# SOC_1_0.net
KiCad netlist of a schematic drawn in EAGLE
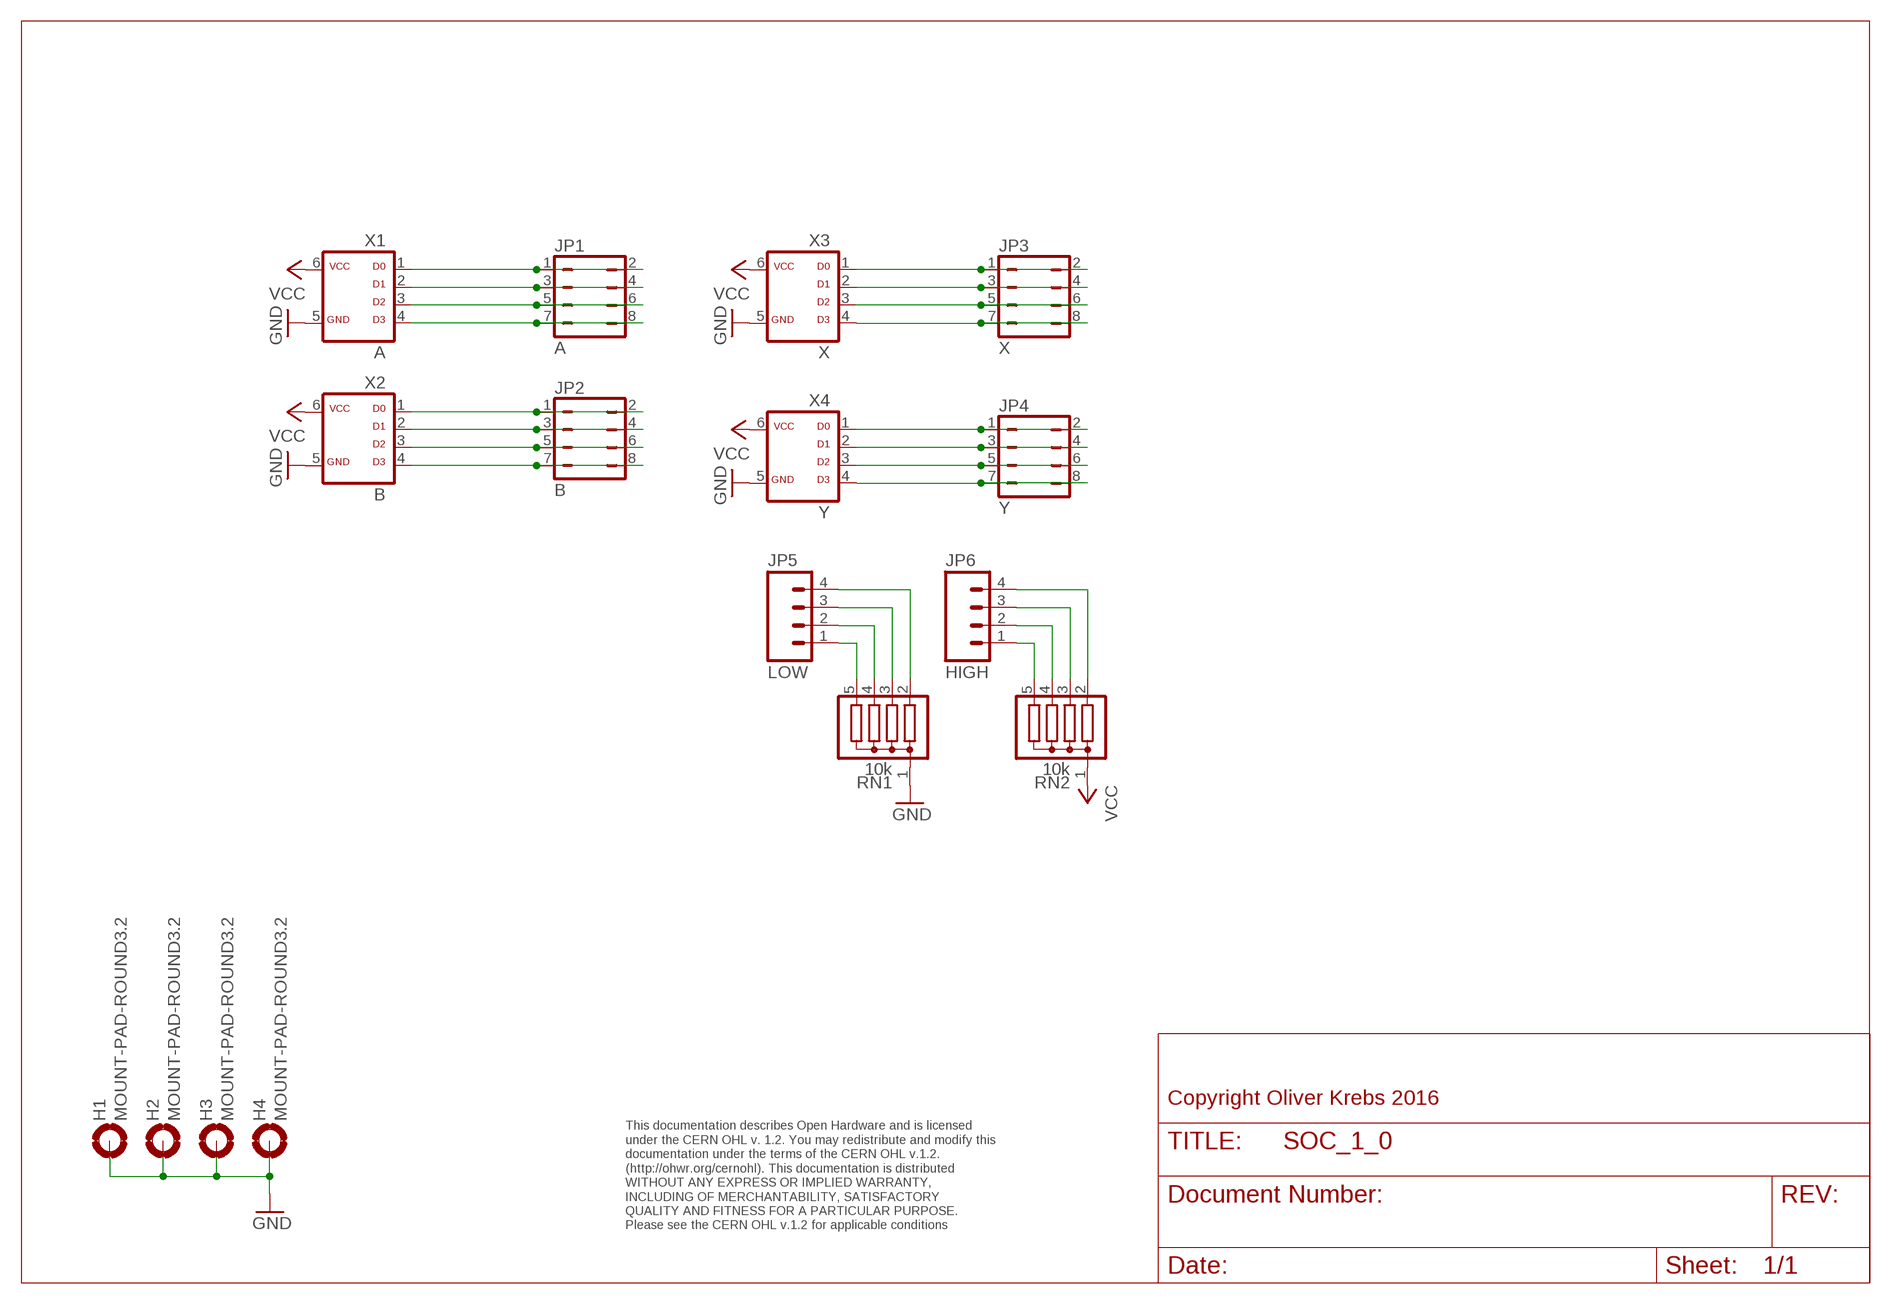
[diagram p0: schematic, sheet 1]

(export (version "E")
  (design (tool "Eeschema 10.0.6"))
  (components
    (comp (ref "H1")
      (value "MOUNT-PAD-ROUND3.2")
      (footprint "eagle-import:3,2-PAD")
      (libsource (lib "eagle-import") (part "MOUNT-PAD-ROUND3.2"))
    )
    (comp (ref "H2")
      (value "MOUNT-PAD-ROUND3.2")
      (footprint "eagle-import:3,2-PAD")
      (libsource (lib "eagle-import") (part "MOUNT-PAD-ROUND3.2"))
    )
    (comp (ref "H3")
      (value "MOUNT-PAD-ROUND3.2")
      (footprint "eagle-import:3,2-PAD")
      (libsource (lib "eagle-import") (part "MOUNT-PAD-ROUND3.2"))
    )
    (comp (ref "H4")
      (value "MOUNT-PAD-ROUND3.2")
      (footprint "eagle-import:3,2-PAD")
      (libsource (lib "eagle-import") (part "MOUNT-PAD-ROUND3.2"))
    )
    (comp (ref "JP1")
      (value "A")
      (footprint "eagle-import:JP4Q")
      (libsource (lib "eagle-import") (part "JP4Q"))
    )
    (comp (ref "JP2")
      (value "B")
      (footprint "eagle-import:JP4Q")
      (libsource (lib "eagle-import") (part "JP4Q"))
    )
    (comp (ref "JP3")
      (value "X")
      (footprint "eagle-import:JP4Q")
      (libsource (lib "eagle-import") (part "JP4Q"))
    )
    (comp (ref "JP4")
      (value "Y")
      (footprint "eagle-import:JP4Q")
      (libsource (lib "eagle-import") (part "JP4Q"))
    )
    (comp (ref "JP5")
      (value "LOW")
      (footprint "eagle-import:1X04")
      (libsource (lib "eagle-import") (part "M04PTH"))
    )
    (comp (ref "JP6")
      (value "HIGH")
      (footprint "eagle-import:1X04")
      (libsource (lib "eagle-import") (part "M04PTH"))
    )
    (comp (ref "RN1")
      (value "10k")
      (footprint "eagle-import:SIL5")
      (libsource (lib "eagle-import") (part "G04R"))
    )
    (comp (ref "RN2")
      (value "10k")
      (footprint "eagle-import:SIL5")
      (libsource (lib "eagle-import") (part "G04R"))
    )
    (comp (ref "X1")
      (value "A")
      (footprint "eagle-import:ML-6")
      (libsource (lib "eagle-import") (part "ML6D"))
    )
    (comp (ref "X2")
      (value "B")
      (footprint "eagle-import:ML-6")
      (libsource (lib "eagle-import") (part "ML6D"))
    )
    (comp (ref "X3")
      (value "X")
      (footprint "eagle-import:ML-6")
      (libsource (lib "eagle-import") (part "ML6D"))
    )
    (comp (ref "X4")
      (value "Y")
      (footprint "eagle-import:ML-6")
      (libsource (lib "eagle-import") (part "ML6D"))
    )
  )
  (nets
    (net (code "1") (name "GND") (class "Default")
      (node (ref "H1") (pin "B3,2") (pinfunction "MOUNT_B3,2") (pintype "passive"))
      (node (ref "H2") (pin "B3,2") (pinfunction "MOUNT_B3,2") (pintype "passive"))
      (node (ref "H3") (pin "B3,2") (pinfunction "MOUNT_B3,2") (pintype "passive"))
      (node (ref "H4") (pin "B3,2") (pinfunction "MOUNT_B3,2") (pintype "passive"))
      (node (ref "RN1") (pin "1") (pinfunction "1_1") (pintype "passive"))
      (node (ref "X1") (pin "5") (pinfunction "5_5") (pintype "passive"))
      (node (ref "X2") (pin "5") (pinfunction "5_5") (pintype "passive"))
      (node (ref "X3") (pin "5") (pinfunction "5_5") (pintype "passive"))
      (node (ref "X4") (pin "5") (pinfunction "5_5") (pintype "passive"))
    )
    (net (code "2") (name "Net-(JP1-Pad1)") (class "Default")
      (node (ref "JP1") (pin "1") (pinfunction "1_1") (pintype "passive"))
      (node (ref "JP1") (pin "2") (pinfunction "2_2") (pintype "passive"))
      (node (ref "X1") (pin "1") (pinfunction "1_1") (pintype "passive"))
    )
    (net (code "3") (name "Net-(JP1-Pad3)") (class "Default")
      (node (ref "JP1") (pin "3") (pinfunction "3_3") (pintype "passive"))
      (node (ref "JP1") (pin "4") (pinfunction "4_4") (pintype "passive"))
      (node (ref "X1") (pin "2") (pinfunction "2_2") (pintype "passive"))
    )
    (net (code "4") (name "Net-(JP1-Pad5)") (class "Default")
      (node (ref "JP1") (pin "5") (pinfunction "5_5") (pintype "passive"))
      (node (ref "JP1") (pin "6") (pinfunction "6_6") (pintype "passive"))
      (node (ref "X1") (pin "3") (pinfunction "3_3") (pintype "passive"))
    )
    (net (code "5") (name "Net-(JP1-Pad7)") (class "Default")
      (node (ref "JP1") (pin "7") (pinfunction "7_7") (pintype "passive"))
      (node (ref "JP1") (pin "8") (pinfunction "8_8") (pintype "passive"))
      (node (ref "X1") (pin "4") (pinfunction "4_4") (pintype "passive"))
    )
    (net (code "6") (name "Net-(JP2-Pad1)") (class "Default")
      (node (ref "JP2") (pin "1") (pinfunction "1_1") (pintype "passive"))
      (node (ref "JP2") (pin "2") (pinfunction "2_2") (pintype "passive"))
      (node (ref "X2") (pin "1") (pinfunction "1_1") (pintype "passive"))
    )
    (net (code "7") (name "Net-(JP2-Pad3)") (class "Default")
      (node (ref "JP2") (pin "3") (pinfunction "3_3") (pintype "passive"))
      (node (ref "JP2") (pin "4") (pinfunction "4_4") (pintype "passive"))
      (node (ref "X2") (pin "2") (pinfunction "2_2") (pintype "passive"))
    )
    (net (code "8") (name "Net-(JP2-Pad5)") (class "Default")
      (node (ref "JP2") (pin "5") (pinfunction "5_5") (pintype "passive"))
      (node (ref "JP2") (pin "6") (pinfunction "6_6") (pintype "passive"))
      (node (ref "X2") (pin "3") (pinfunction "3_3") (pintype "passive"))
    )
    (net (code "9") (name "Net-(JP2-Pad7)") (class "Default")
      (node (ref "JP2") (pin "7") (pinfunction "7_7") (pintype "passive"))
      (node (ref "JP2") (pin "8") (pinfunction "8_8") (pintype "passive"))
      (node (ref "X2") (pin "4") (pinfunction "4_4") (pintype "passive"))
    )
    (net (code "10") (name "Net-(JP3-Pad1)") (class "Default")
      (node (ref "JP3") (pin "1") (pinfunction "1_1") (pintype "passive"))
      (node (ref "JP3") (pin "2") (pinfunction "2_2") (pintype "passive"))
      (node (ref "X3") (pin "1") (pinfunction "1_1") (pintype "passive"))
    )
    (net (code "11") (name "Net-(JP3-Pad3)") (class "Default")
      (node (ref "JP3") (pin "3") (pinfunction "3_3") (pintype "passive"))
      (node (ref "JP3") (pin "4") (pinfunction "4_4") (pintype "passive"))
      (node (ref "X3") (pin "2") (pinfunction "2_2") (pintype "passive"))
    )
    (net (code "12") (name "Net-(JP3-Pad5)") (class "Default")
      (node (ref "JP3") (pin "5") (pinfunction "5_5") (pintype "passive"))
      (node (ref "JP3") (pin "6") (pinfunction "6_6") (pintype "passive"))
      (node (ref "X3") (pin "3") (pinfunction "3_3") (pintype "passive"))
    )
    (net (code "13") (name "Net-(JP3-Pad7)") (class "Default")
      (node (ref "JP3") (pin "7") (pinfunction "7_7") (pintype "passive"))
      (node (ref "JP3") (pin "8") (pinfunction "8_8") (pintype "passive"))
      (node (ref "X3") (pin "4") (pinfunction "4_4") (pintype "passive"))
    )
    (net (code "14") (name "Net-(JP4-Pad1)") (class "Default")
      (node (ref "JP4") (pin "1") (pinfunction "1_1") (pintype "passive"))
      (node (ref "JP4") (pin "2") (pinfunction "2_2") (pintype "passive"))
      (node (ref "X4") (pin "1") (pinfunction "1_1") (pintype "passive"))
    )
    (net (code "15") (name "Net-(JP4-Pad3)") (class "Default")
      (node (ref "JP4") (pin "3") (pinfunction "3_3") (pintype "passive"))
      (node (ref "JP4") (pin "4") (pinfunction "4_4") (pintype "passive"))
      (node (ref "X4") (pin "2") (pinfunction "2_2") (pintype "passive"))
    )
    (net (code "16") (name "Net-(JP4-Pad5)") (class "Default")
      (node (ref "JP4") (pin "5") (pinfunction "5_5") (pintype "passive"))
      (node (ref "JP4") (pin "6") (pinfunction "6_6") (pintype "passive"))
      (node (ref "X4") (pin "3") (pinfunction "3_3") (pintype "passive"))
    )
    (net (code "17") (name "Net-(JP4-Pad7)") (class "Default")
      (node (ref "JP4") (pin "7") (pinfunction "7_7") (pintype "passive"))
      (node (ref "JP4") (pin "8") (pinfunction "8_8") (pintype "passive"))
      (node (ref "X4") (pin "4") (pinfunction "4_4") (pintype "passive"))
    )
    (net (code "18") (name "Net-(JP5-Pad1)") (class "Default")
      (node (ref "JP5") (pin "1") (pinfunction "1_1") (pintype "passive"))
      (node (ref "RN1") (pin "5") (pinfunction "5_5") (pintype "passive"))
    )
    (net (code "19") (name "Net-(JP5-Pad2)") (class "Default")
      (node (ref "JP5") (pin "2") (pinfunction "2_2") (pintype "passive"))
      (node (ref "RN1") (pin "4") (pinfunction "4_4") (pintype "passive"))
    )
    (net (code "20") (name "Net-(JP5-Pad3)") (class "Default")
      (node (ref "JP5") (pin "3") (pinfunction "3_3") (pintype "passive"))
      (node (ref "RN1") (pin "3") (pinfunction "3_3") (pintype "passive"))
    )
    (net (code "21") (name "Net-(JP5-Pad4)") (class "Default")
      (node (ref "JP5") (pin "4") (pinfunction "4_4") (pintype "passive"))
      (node (ref "RN1") (pin "2") (pinfunction "2_2") (pintype "passive"))
    )
    (net (code "22") (name "Net-(JP6-Pad1)") (class "Default")
      (node (ref "JP6") (pin "1") (pinfunction "1_1") (pintype "passive"))
      (node (ref "RN2") (pin "5") (pinfunction "5_5") (pintype "passive"))
    )
    (net (code "23") (name "Net-(JP6-Pad2)") (class "Default")
      (node (ref "JP6") (pin "2") (pinfunction "2_2") (pintype "passive"))
      (node (ref "RN2") (pin "4") (pinfunction "4_4") (pintype "passive"))
    )
    (net (code "24") (name "Net-(JP6-Pad3)") (class "Default")
      (node (ref "JP6") (pin "3") (pinfunction "3_3") (pintype "passive"))
      (node (ref "RN2") (pin "3") (pinfunction "3_3") (pintype "passive"))
    )
    (net (code "25") (name "Net-(JP6-Pad4)") (class "Default")
      (node (ref "JP6") (pin "4") (pinfunction "4_4") (pintype "passive"))
      (node (ref "RN2") (pin "2") (pinfunction "2_2") (pintype "passive"))
    )
    (net (code "26") (name "VCC") (class "Default")
      (node (ref "RN2") (pin "1") (pinfunction "1_1") (pintype "passive"))
      (node (ref "X1") (pin "6") (pinfunction "6_6") (pintype "passive"))
      (node (ref "X2") (pin "6") (pinfunction "6_6") (pintype "passive"))
      (node (ref "X3") (pin "6") (pinfunction "6_6") (pintype "passive"))
      (node (ref "X4") (pin "6") (pinfunction "6_6") (pintype "passive"))
    )
  )
)
